# bwlMotorSpeed.net
KiCad netlist of a schematic drawn in EAGLE
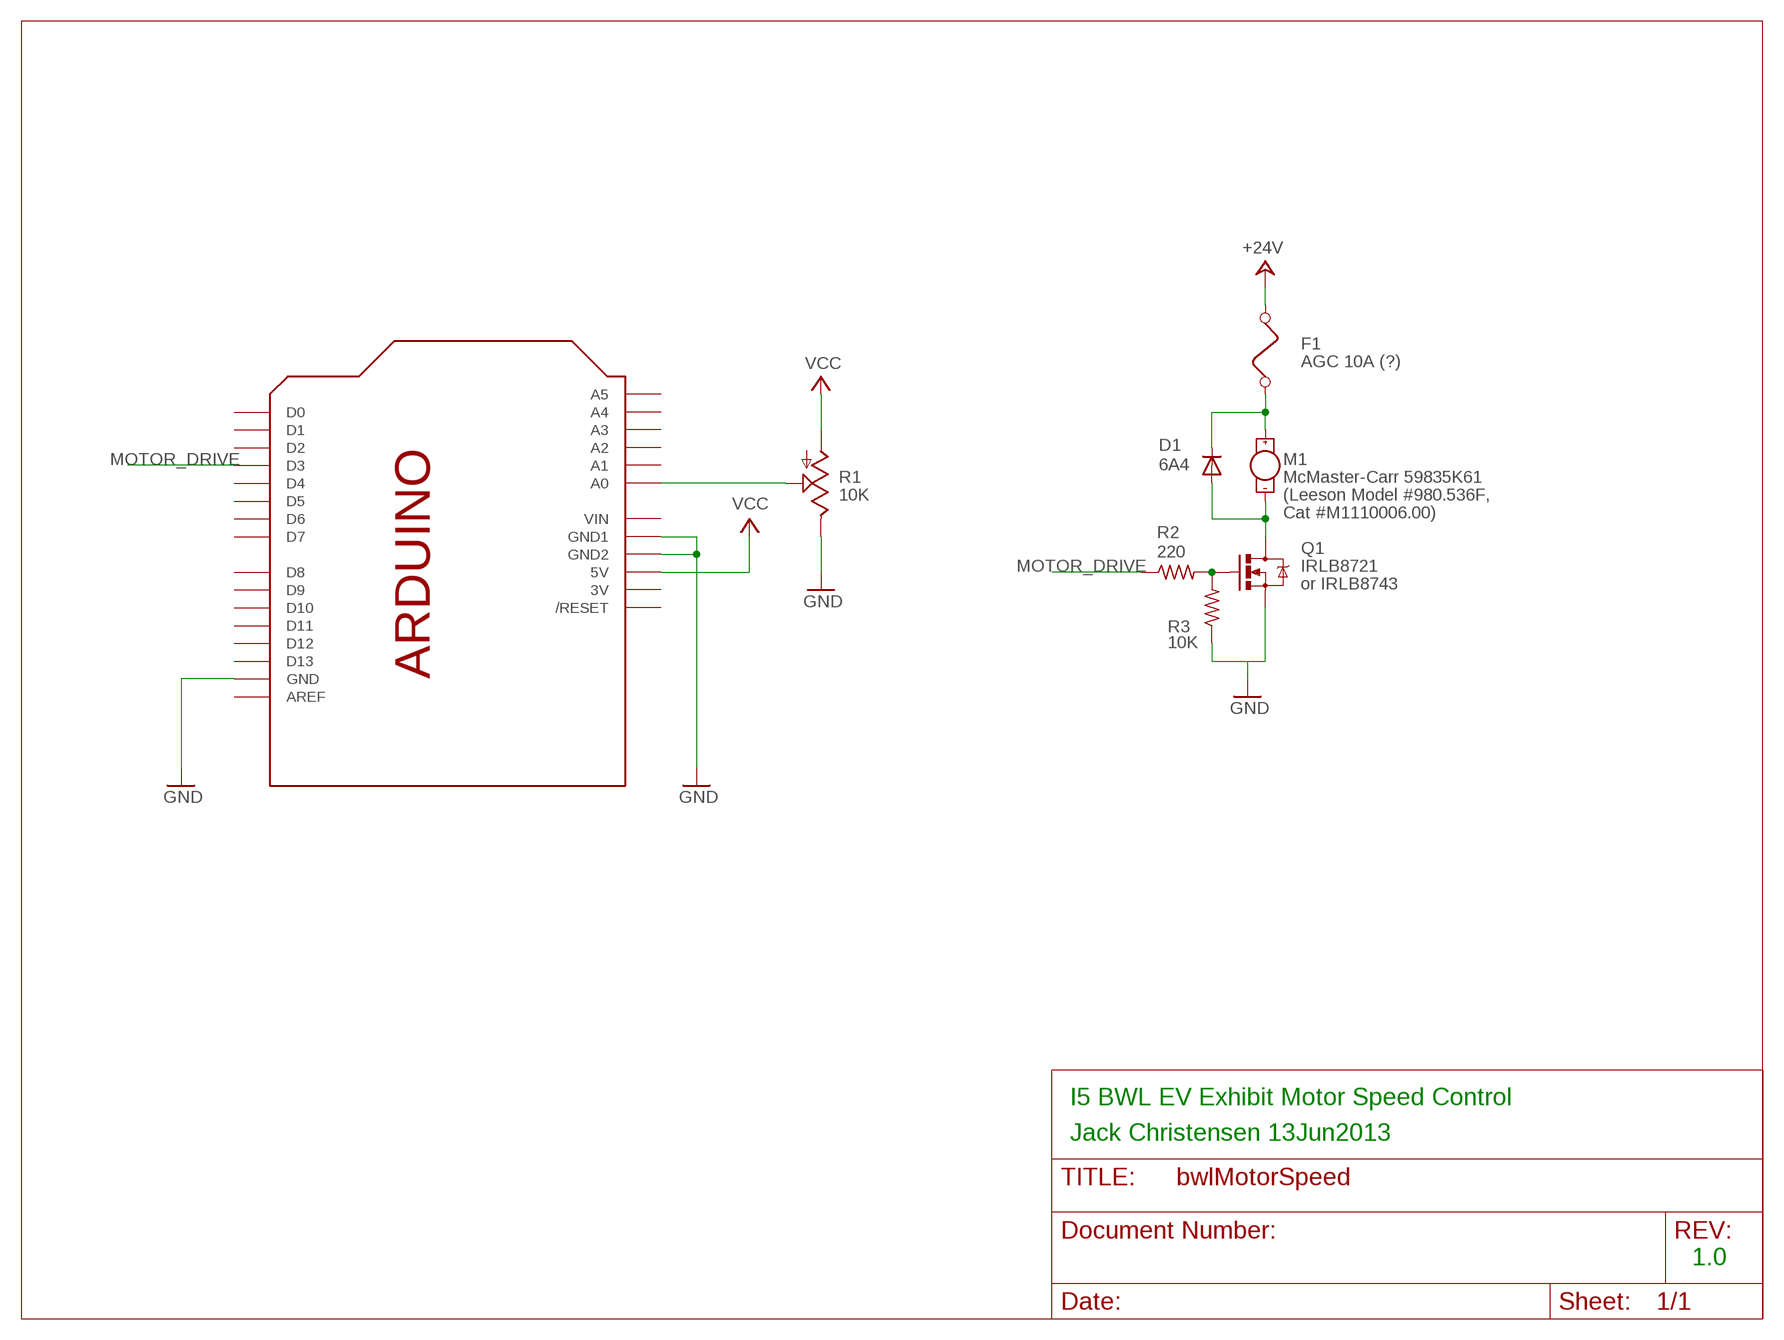
[diagram p0: schematic, sheet 1]

(export (version "E")
  (design (tool "Eeschema 10.0.6"))
  (components
    (comp (ref "D1")
      (value "6A4")
      (footprint "eagle-import:1N400X")
      (libsource (lib "eagle-import") (part "DIODE1N400X"))
    )
    (comp (ref "F1")
      (value "AGC 10A (?)")
      (footprint "eagle-import:FUSE")
      (libsource (lib "eagle-import") (part "FUSE"))
    )
    (comp (ref "M1")
      (value "McMaster-Carr 59835K61")
      (footprint "eagle-import:VIBE-MOTOR-10MM")
      (libsource (lib "eagle-import") (part "MOTOR10MM"))
    )
    (comp (ref "Q1")
      (value "IRLB8721")
      (footprint "eagle-import:TO-92")
      (libsource (lib "eagle-import") (part "MOSFET-NCHANNELPTH"))
    )
    (comp (ref "R1")
      (value "10K")
      (footprint "eagle-import:TRIMPOT-3386P")
      (libsource (lib "eagle-import") (part "TRIMPOT-3386P3386P"))
    )
    (comp (ref "R2")
      (value "220")
      (footprint "eagle-import:M0805")
      (libsource (lib "eagle-import") (part "R-US_M0805"))
    )
    (comp (ref "R3")
      (value "10K")
      (footprint "eagle-import:M0805")
      (libsource (lib "eagle-import") (part "R-US_M0805"))
    )
    (comp (ref "U$1")
      (value "ARDUINOUNO")
      (footprint "eagle-import:ARDUINO")
      (libsource (lib "eagle-import") (part "ARDUINOUNO"))
    )
  )
  (nets
    (net (code "1") (name "+24V") (class "Default")
      (node (ref "F1") (pin "2") (pinfunction "2_2") (pintype "passive"))
    )
    (net (code "2") (name "/3V") (class "Default")
      (node (ref "U$1") (pin "3V") (pinfunction "3V_3V") (pintype "power_in"))
    )
    (net (code "3") (name "/MOTOR_DRIVE") (class "Default")
      (node (ref "R2") (pin "1") (pinfunction "1_1") (pintype "passive"))
      (node (ref "U$1") (pin "D3") (pinfunction "D3_D3") (pintype "bidirectional"))
    )
    (net (code "4") (name "/VIN") (class "Default")
      (node (ref "U$1") (pin "VIN") (pinfunction "VIN_VIN") (pintype "power_in"))
    )
    (net (code "5") (name "GND") (class "Default")
      (node (ref "Q1") (pin "2") (pinfunction "S_2") (pintype "passive"))
      (node (ref "R1") (pin "1") (pinfunction "E_1") (pintype "passive"))
      (node (ref "R3") (pin "1") (pinfunction "1_1") (pintype "passive"))
      (node (ref "U$1") (pin "GND") (pinfunction "GND_GND") (pintype "power_in"))
      (node (ref "U$1") (pin "GND1") (pinfunction "GND1_GND1") (pintype "power_in"))
      (node (ref "U$1") (pin "GND2") (pinfunction "GND2_GND2") (pintype "power_in"))
    )
    (net (code "6") (name "Net-(D1-PadK)") (class "Default")
      (node (ref "D1") (pin "K") (pinfunction "K_K") (pintype "passive"))
      (node (ref "F1") (pin "1") (pinfunction "1_1") (pintype "passive"))
      (node (ref "M1") (pin "+") (pinfunction "+_+") (pintype "bidirectional"))
    )
    (net (code "7") (name "Net-(Q1-D)") (class "Default")
      (node (ref "D1") (pin "A") (pinfunction "A_A") (pintype "passive"))
      (node (ref "M1") (pin "-") (pinfunction "-_-") (pintype "bidirectional"))
      (node (ref "Q1") (pin "1") (pinfunction "D_1") (pintype "passive"))
    )
    (net (code "8") (name "Net-(Q1-G)") (class "Default")
      (node (ref "Q1") (pin "3") (pinfunction "G_3") (pintype "passive"))
      (node (ref "R2") (pin "2") (pinfunction "2_2") (pintype "passive"))
      (node (ref "R3") (pin "2") (pinfunction "2_2") (pintype "passive"))
    )
    (net (code "9") (name "Net-(R1-S)") (class "Default")
      (node (ref "R1") (pin "2") (pinfunction "S_2") (pintype "passive"))
      (node (ref "U$1") (pin "A0") (pinfunction "A0_A0") (pintype "bidirectional"))
    )
    (net (code "10") (name "VCC") (class "Default")
      (node (ref "R1") (pin "3") (pinfunction "A_3") (pintype "passive"))
      (node (ref "U$1") (pin "5V") (pinfunction "5V_5V") (pintype "power_in"))
    )
    (net (code "11") (name "unconnected-(U$1-PadA1)") (class "Default")
      (node (ref "U$1") (pin "A1") (pinfunction "A1_A1") (pintype "bidirectional"))
    )
    (net (code "12") (name "unconnected-(U$1-PadA2)") (class "Default")
      (node (ref "U$1") (pin "A2") (pinfunction "A2_A2") (pintype "bidirectional"))
    )
    (net (code "13") (name "unconnected-(U$1-PadA3)") (class "Default")
      (node (ref "U$1") (pin "A3") (pinfunction "A3_A3") (pintype "bidirectional"))
    )
    (net (code "14") (name "unconnected-(U$1-PadA4)") (class "Default")
      (node (ref "U$1") (pin "A4") (pinfunction "A4_A4") (pintype "bidirectional"))
    )
    (net (code "15") (name "unconnected-(U$1-PadA5)") (class "Default")
      (node (ref "U$1") (pin "A5") (pinfunction "A5_A5") (pintype "bidirectional"))
    )
    (net (code "16") (name "unconnected-(U$1-PadAREF)") (class "Default")
      (node (ref "U$1") (pin "AREF") (pinfunction "AREF_AREF") (pintype "bidirectional"))
    )
    (net (code "17") (name "unconnected-(U$1-PadD0)") (class "Default")
      (node (ref "U$1") (pin "D0") (pinfunction "D0_D0") (pintype "bidirectional"))
    )
    (net (code "18") (name "unconnected-(U$1-PadD1)") (class "Default")
      (node (ref "U$1") (pin "D1") (pinfunction "D1_D1") (pintype "bidirectional"))
    )
    (net (code "19") (name "unconnected-(U$1-PadD2)") (class "Default")
      (node (ref "U$1") (pin "D2") (pinfunction "D2_D2") (pintype "bidirectional"))
    )
    (net (code "20") (name "unconnected-(U$1-PadD4)") (class "Default")
      (node (ref "U$1") (pin "D4") (pinfunction "D4_D4") (pintype "bidirectional"))
    )
    (net (code "21") (name "unconnected-(U$1-PadD5)") (class "Default")
      (node (ref "U$1") (pin "D5") (pinfunction "D5_D5") (pintype "bidirectional"))
    )
    (net (code "22") (name "unconnected-(U$1-PadD6)") (class "Default")
      (node (ref "U$1") (pin "D6") (pinfunction "D6_D6") (pintype "bidirectional"))
    )
    (net (code "23") (name "unconnected-(U$1-PadD7)") (class "Default")
      (node (ref "U$1") (pin "D7") (pinfunction "D7_D7") (pintype "bidirectional"))
    )
    (net (code "24") (name "unconnected-(U$1-PadD8)") (class "Default")
      (node (ref "U$1") (pin "D8") (pinfunction "D8_D8") (pintype "bidirectional"))
    )
    (net (code "25") (name "unconnected-(U$1-PadD9)") (class "Default")
      (node (ref "U$1") (pin "D9") (pinfunction "D9_D9") (pintype "bidirectional"))
    )
    (net (code "26") (name "unconnected-(U$1-PadD10)") (class "Default")
      (node (ref "U$1") (pin "D10") (pinfunction "D10_D10") (pintype "bidirectional"))
    )
    (net (code "27") (name "unconnected-(U$1-PadD11)") (class "Default")
      (node (ref "U$1") (pin "D11") (pinfunction "D11_D11") (pintype "bidirectional"))
    )
    (net (code "28") (name "unconnected-(U$1-PadD12)") (class "Default")
      (node (ref "U$1") (pin "D12") (pinfunction "D12_D12") (pintype "bidirectional"))
    )
    (net (code "29") (name "unconnected-(U$1-PadD13)") (class "Default")
      (node (ref "U$1") (pin "D13") (pinfunction "D13_D13") (pintype "bidirectional"))
    )
    (net (code "30") (name "unconnected-(U$1-{slash}RESET-PadRESET)") (class "Default")
      (node (ref "U$1") (pin "RESET") (pinfunction "/RESET_RESET") (pintype "bidirectional"))
    )
  )
)
